# Proiect_TSC_SCHEMATIC.net
KiCad netlist of a schematic drawn in EAGLE
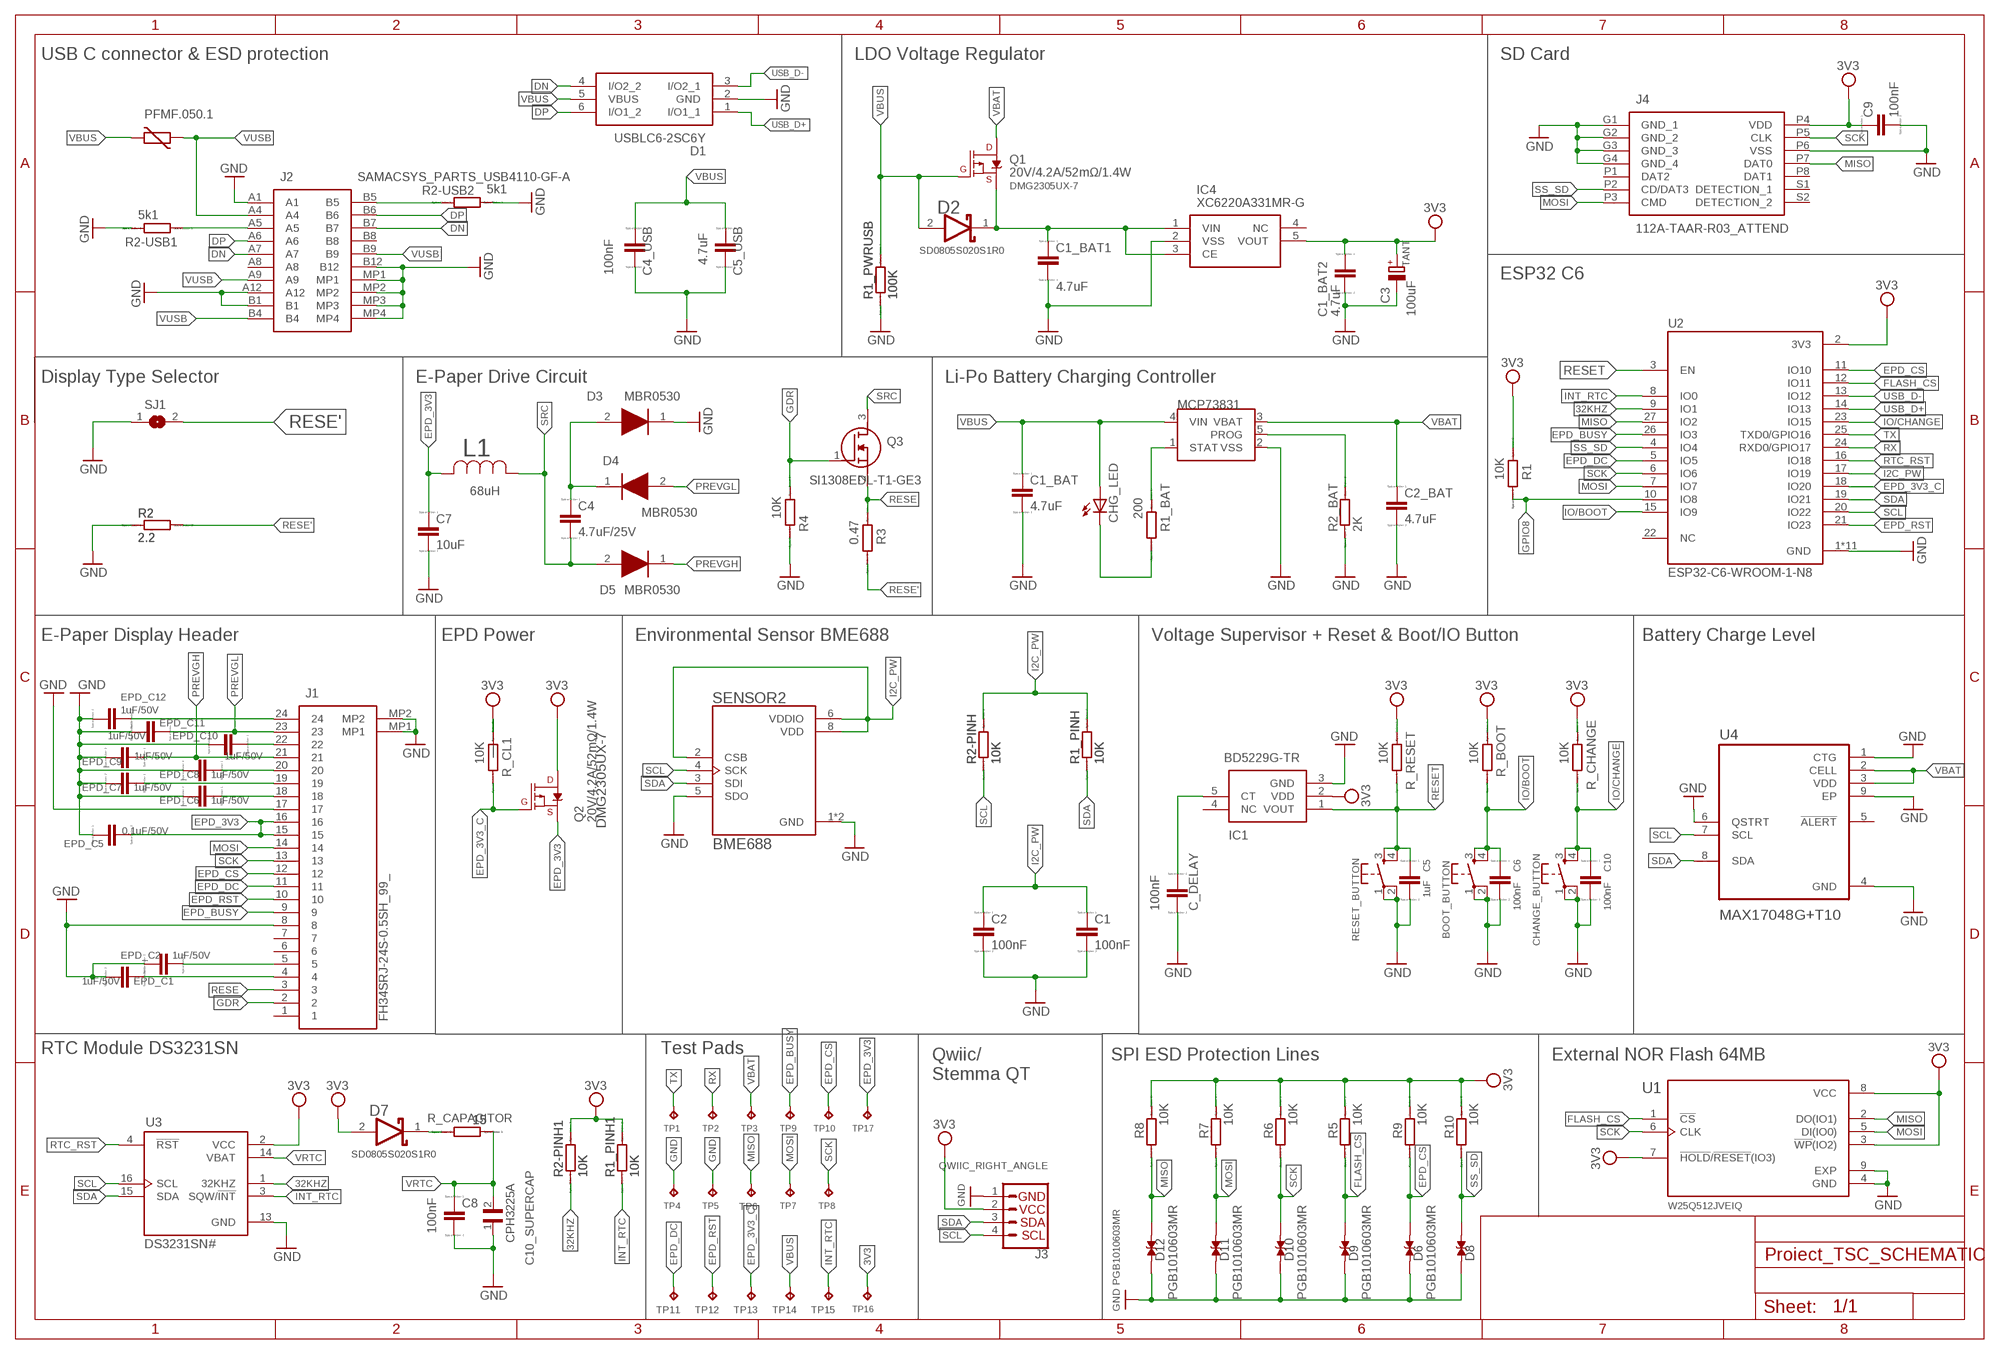
[diagram p0: schematic, sheet 1]

(export (version "E")
  (design (tool "Eeschema 10.0.6"))
  (components
    (comp (ref "BOOT_BUTTON")
      (value "BUTTON_CUSYOMV1")
      (footprint "eagle-import:MYBUTTON")
      (libsource (lib "eagle-import") (part "BUTTON_CUSYOMV1"))
    )
    (comp (ref "C1")
      (value "100nF")
      (footprint "eagle-import:ESP32_WROVER_EAGLE-LTSPICE_C0402")
      (libsource (lib "eagle-import") (part "ESP32_WROVER_EAGLE-LTSPICE_CC0402"))
    )
    (comp (ref "C1_BAT")
      (value "4.7uF")
      (footprint "eagle-import:ESP32_WROVER_EAGLE-LTSPICE_C0402")
      (libsource (lib "eagle-import") (part "ESP32_WROVER_EAGLE-LTSPICE_CC0402"))
    )
    (comp (ref "C1_BAT1")
      (value "4.7uF")
      (footprint "eagle-import:ESP32_WROVER_EAGLE-LTSPICE_C0402")
      (libsource (lib "eagle-import") (part "ESP32_WROVER_EAGLE-LTSPICE_CC0402"))
    )
    (comp (ref "C1_BAT2")
      (value "4.7uF")
      (footprint "eagle-import:ESP32_WROVER_EAGLE-LTSPICE_C0402")
      (libsource (lib "eagle-import") (part "ESP32_WROVER_EAGLE-LTSPICE_CC0402"))
    )
    (comp (ref "C2")
      (value "100nF")
      (footprint "eagle-import:ESP32_WROVER_EAGLE-LTSPICE_C0402")
      (libsource (lib "eagle-import") (part "ESP32_WROVER_EAGLE-LTSPICE_CC0402"))
    )
    (comp (ref "C2_BAT")
      (value "4.7uF")
      (footprint "eagle-import:ESP32_WROVER_EAGLE-LTSPICE_C0402")
      (libsource (lib "eagle-import") (part "ESP32_WROVER_EAGLE-LTSPICE_CC0402"))
    )
    (comp (ref "C3")
      (value "100uF")
      (footprint "eagle-import:RCL_CT3528")
      (libsource (lib "eagle-import") (part "RCL_CPOL-EUCT3528"))
    )
    (comp (ref "C4")
      (value "4.7uF/25V")
      (footprint "eagle-import:ESP32_WROVER_EAGLE-LTSPICE_C0402")
      (libsource (lib "eagle-import") (part "ESP32_WROVER_EAGLE-LTSPICE_CC0402"))
    )
    (comp (ref "C4_USB")
      (value "100nF")
      (footprint "eagle-import:EAGLE-LTSPICE_C0402")
      (libsource (lib "eagle-import") (part "EAGLE-LTSPICE_CC0402"))
    )
    (comp (ref "C5")
      (value "1uF")
      (footprint "eagle-import:ESP32_WROVER_EAGLE-LTSPICE_C0402")
      (libsource (lib "eagle-import") (part "ESP32_WROVER_EAGLE-LTSPICE_CC0402"))
    )
    (comp (ref "C5_USB")
      (value "4.7uF")
      (footprint "eagle-import:EAGLE-LTSPICE_C0402")
      (libsource (lib "eagle-import") (part "EAGLE-LTSPICE_CC0402"))
    )
    (comp (ref "C6")
      (value "100nF")
      (footprint "eagle-import:ESP32_WROVER_EAGLE-LTSPICE_C0402")
      (libsource (lib "eagle-import") (part "ESP32_WROVER_EAGLE-LTSPICE_CC0402"))
    )
    (comp (ref "C7")
      (value "10uF")
      (footprint "eagle-import:ESP32_WROVER_EAGLE-LTSPICE_C0402")
      (libsource (lib "eagle-import") (part "ESP32_WROVER_EAGLE-LTSPICE_CC0402"))
    )
    (comp (ref "C8")
      (value "100nF")
      (footprint "eagle-import:ESP32_WROVER_EAGLE-LTSPICE_C0402")
      (libsource (lib "eagle-import") (part "ESP32_WROVER_EAGLE-LTSPICE_CC0402"))
    )
    (comp (ref "C9")
      (value "100nF")
      (footprint "eagle-import:ESP32_WROVER_EAGLE-LTSPICE_C0402")
      (libsource (lib "eagle-import") (part "ESP32_WROVER_EAGLE-LTSPICE_CC0402"))
    )
    (comp (ref "C10")
      (value "100nF")
      (footprint "eagle-import:ESP32_WROVER_EAGLE-LTSPICE_C0402")
      (libsource (lib "eagle-import") (part "ESP32_WROVER_EAGLE-LTSPICE_CC0402"))
    )
    (comp (ref "C10_SUPERCAP")
      (value "CPH3225A")
      (footprint "eagle-import:CAPCP3225X100N")
      (fields (field (name "MF") "Seiko Instruments"))
      (libsource (lib "eagle-import") (part "CPH3225A"))
    )
    (comp (ref "CHANGE_BUTTON")
      (value "CHANGE_BUTTON")
      (footprint "eagle-import:MYBUTTON")
      (libsource (lib "eagle-import") (part "BUTTON_CUSYOMV1"))
    )
    (comp (ref "CHG_LED")
      (value "ADAFRUIT_LEDCHIP-LED0603")
      (footprint "eagle-import:ADAFRUIT_CHIP-LED0603")
      (libsource (lib "eagle-import") (part "ADAFRUIT_LEDCHIP-LED0603"))
    )
    (comp (ref "C_DELAY")
      (value "100nF")
      (footprint "eagle-import:ESP32_WROVER_EAGLE-LTSPICE_C0402")
      (libsource (lib "eagle-import") (part "ESP32_WROVER_EAGLE-LTSPICE_CC0402"))
    )
    (comp (ref "D1")
      (value "USBLC6-2SC6Y")
      (footprint "eagle-import:SOT95P280X145-6N")
      (fields (field (name "MF") "STMicroelectronics"))
      (libsource (lib "eagle-import") (part "USBLC6-2SC6Y"))
    )
    (comp (ref "D2")
      (value "ESP32_WROVER_AVX---SD0805S020S1R0_AVX_SD0805S020S1R0_0_0AVX_SD0805S020S1R0_0_0")
      (footprint "eagle-import:ESP32_WROVER_AVX---SD0805S020S1R0_AVX_SD0805S020S1R0_0")
      (fields
        (field (name "DIGIKEY_PART_NUMBER") "478-7800-1-ND")
        (field (name "MF") "AVX")
        (field (name "MOUSER_PART_NUMBER") "581-SD0805S020S1R0")
      )
      (libsource (lib "eagle-import") (part "ESP32_WROVER_AVX---SD0805S020S1R0_AVX_SD0805S020S1R0_0_0AVX_SD0805S020S1R0_0_0"))
    )
    (comp (ref "D3")
      (value "MBR0530")
      (footprint "eagle-import:SOD3716X135N")
      (fields (field (name "MF") "ON Semiconductor"))
      (libsource (lib "eagle-import") (part "MBR0530"))
    )
    (comp (ref "D4")
      (value "MBR0530")
      (footprint "eagle-import:SOD3716X135N")
      (fields (field (name "MF") "ON Semiconductor"))
      (libsource (lib "eagle-import") (part "MBR0530"))
    )
    (comp (ref "D5")
      (value "MBR0530")
      (footprint "eagle-import:SOD3716X135N")
      (fields (field (name "MF") "ON Semiconductor"))
      (libsource (lib "eagle-import") (part "MBR0530"))
    )
    (comp (ref "D6")
      (value "PGB1010603MR")
      (footprint "eagle-import:DIOC1608X36N")
      (fields (field (name "MF") "Littelfuse Inc."))
      (libsource (lib "eagle-import") (part "PGB1010603MR"))
    )
    (comp (ref "D7")
      (value "SD0805S020S1R0")
      (footprint "eagle-import:ESP32_WROVER_AVX---SD0805S020S1R0_AVX_SD0805S020S1R0_0")
      (fields
        (field (name "DIGIKEY_PART_NUMBER") "478-7800-1-ND")
        (field (name "MF") "AVX")
        (field (name "MOUSER_PART_NUMBER") "581-SD0805S020S1R0")
      )
      (libsource (lib "eagle-import") (part "ESP32_WROVER_AVX---SD0805S020S1R0_AVX_SD0805S020S1R0_0_0AVX_SD0805S020S1R0_0_0"))
    )
    (comp (ref "D8")
      (value "PGB1010603MR")
      (footprint "eagle-import:DIOC1608X36N")
      (fields (field (name "MF") "Littelfuse Inc."))
      (libsource (lib "eagle-import") (part "PGB1010603MR"))
    )
    (comp (ref "D9")
      (value "PGB1010603MR")
      (footprint "eagle-import:DIOC1608X36N")
      (fields (field (name "MF") "Littelfuse Inc."))
      (libsource (lib "eagle-import") (part "PGB1010603MR"))
    )
    (comp (ref "D10")
      (value "PGB1010603MR")
      (footprint "eagle-import:DIOC1608X36N")
      (fields (field (name "MF") "Littelfuse Inc."))
      (libsource (lib "eagle-import") (part "PGB1010603MR"))
    )
    (comp (ref "D11")
      (value "PGB1010603MR")
      (footprint "eagle-import:DIOC1608X36N")
      (fields (field (name "MF") "Littelfuse Inc."))
      (libsource (lib "eagle-import") (part "PGB1010603MR"))
    )
    (comp (ref "D12")
      (value "PGB1010603MR")
      (footprint "eagle-import:DIOC1608X36N")
      (fields (field (name "MF") "Littelfuse Inc."))
      (libsource (lib "eagle-import") (part "PGB1010603MR"))
    )
    (comp (ref "EPD_C1")
      (value "1uF/50V")
      (footprint "eagle-import:ESP32_WROVER_EAGLE-LTSPICE_C0402")
      (libsource (lib "eagle-import") (part "ESP32_WROVER_EAGLE-LTSPICE_CC0402"))
    )
    (comp (ref "EPD_C2")
      (value "1uF/50V")
      (footprint "eagle-import:ESP32_WROVER_EAGLE-LTSPICE_C0402")
      (libsource (lib "eagle-import") (part "ESP32_WROVER_EAGLE-LTSPICE_CC0402"))
    )
    (comp (ref "EPD_C5")
      (value "0.1uF/50V")
      (footprint "eagle-import:ESP32_WROVER_EAGLE-LTSPICE_C0402")
      (libsource (lib "eagle-import") (part "ESP32_WROVER_EAGLE-LTSPICE_CC0402"))
    )
    (comp (ref "EPD_C6")
      (value "1uF/50V")
      (footprint "eagle-import:ESP32_WROVER_EAGLE-LTSPICE_C0402")
      (libsource (lib "eagle-import") (part "ESP32_WROVER_EAGLE-LTSPICE_CC0402"))
    )
    (comp (ref "EPD_C7")
      (value "1uF/50V")
      (footprint "eagle-import:ESP32_WROVER_EAGLE-LTSPICE_C0402")
      (libsource (lib "eagle-import") (part "ESP32_WROVER_EAGLE-LTSPICE_CC0402"))
    )
    (comp (ref "EPD_C8")
      (value "1uF/50V")
      (footprint "eagle-import:ESP32_WROVER_EAGLE-LTSPICE_C0402")
      (libsource (lib "eagle-import") (part "ESP32_WROVER_EAGLE-LTSPICE_CC0402"))
    )
    (comp (ref "EPD_C9")
      (value "1uF/50V")
      (footprint "eagle-import:ESP32_WROVER_EAGLE-LTSPICE_C0402")
      (libsource (lib "eagle-import") (part "ESP32_WROVER_EAGLE-LTSPICE_CC0402"))
    )
    (comp (ref "EPD_C10")
      (value "1uF/50V")
      (footprint "eagle-import:ESP32_WROVER_EAGLE-LTSPICE_C0402")
      (libsource (lib "eagle-import") (part "ESP32_WROVER_EAGLE-LTSPICE_CC0402"))
    )
    (comp (ref "EPD_C11")
      (value "1uF/50V")
      (footprint "eagle-import:ESP32_WROVER_EAGLE-LTSPICE_C0402")
      (libsource (lib "eagle-import") (part "ESP32_WROVER_EAGLE-LTSPICE_CC0402"))
    )
    (comp (ref "EPD_C12")
      (value "1uF/50V")
      (footprint "eagle-import:ESP32_WROVER_EAGLE-LTSPICE_C0402")
      (libsource (lib "eagle-import") (part "ESP32_WROVER_EAGLE-LTSPICE_CC0402"))
    )
    (comp (ref "IC1")
      (value "BD5229G-TR")
      (footprint "eagle-import:SOT95P280X125-5N")
      (fields (field (name "MOUSER_PART_NUMBER") "755-BD5229G-TR"))
      (libsource (lib "eagle-import") (part "BD5229G-TR"))
    )
    (comp (ref "IC4")
      (value "XC6220A331MR-G")
      (footprint "eagle-import:SOT95P280X120-5N")
      (fields (field (name "MOUSER_PART_NUMBER") "865-XC6220A331MR-G"))
      (libsource (lib "eagle-import") (part "XC6220A331MR-G"))
    )
    (comp (ref "J1")
      (value "FH34SRJ-24S-0.5SH_99_")
      (footprint "eagle-import:FH34SRJ24S05SH99")
      (fields
        (field (name "MANUFACTURER_PART_NUMBER") "FH34SRJ-24S-0.5SH(99)")
        (field (name "MOUSER_PART_NUMBER") "798-FH34SRJ24S05SH99")
      )
      (libsource (lib "eagle-import") (part "FH34SRJ-24S-0.5SH_99_"))
    )
    (comp (ref "J2")
      (value "SAMACSYS_PARTS_USB4110-GF-A")
      (footprint "eagle-import:SAMACSYS_PARTS_USB4110GFA")
      (fields
        (field (name "MANUFACTURER_PART_NUMBER") "USB4110-GF-A")
        (field (name "MOUSER_PART_NUMBER") "640-USB4110-GF-A")
      )
      (libsource (lib "eagle-import") (part "SAMACSYS_PARTS_USB4110-GF-A"))
    )
    (comp (ref "J3")
      (value "QWIIC_RIGHT_ANGLE")
      (footprint "eagle-import:JST04_1MM_RA")
      (libsource (lib "eagle-import") (part "QWIIC_CONNECTORJS-1MM"))
    )
    (comp (ref "J4")
      (value "112A-TAAR-R03_ATTEND")
      (footprint "eagle-import:112ATAARR03ATTEND")
      (fields (field (name "MANUFACTURER_PART_NUMBER") "112A-TAAR-R03 ATTEND"))
      (libsource (lib "eagle-import") (part "112A-TAAR-R03_ATTEND"))
    )
    (comp (ref "L1")
      (value "68uH")
      (footprint "eagle-import:IND_4828-WE-TPC_WRE")
      (fields
        (field (name "MANUFACTURER_PART_NUMBER") "744043680")
        (field (name "COPYRIGHT") "Copyright (C) 2024 Ultra Librarian. All rights reserved.")
      )
      (libsource (lib "eagle-import") (part "744043680IND_4828-WE-TPC_WRE"))
    )
    (comp (ref "MCP73831")
      (value "MCP73831")
      (footprint "eagle-import:ESP32_WROVER_SPARKFUN-IC-POWER_SOT23-5")
      (libsource (lib "eagle-import") (part "ESP32_WROVER_SPARKFUN-IC-POWER_MCP73831"))
    )
    (comp (ref "PFMF.050.1")
      (value "ESP32C6_VARISTORCN1812")
      (footprint "eagle-import:ESP32C6_VARISTOR_CT_CN1812")
      (libsource (lib "eagle-import") (part "ESP32C6_VARISTORCN1812"))
    )
    (comp (ref "Q1")
      (value "20V/4.2A/52mΩ/1.4W")
      (footprint "eagle-import:ESP32_WROVER_SPARKFUN-DISCRETESEMI_SOT23-3")
      (libsource (lib "eagle-import") (part "ESP32_WROVER_SPARKFUN-DISCRETESEMI_MOSFET_PCH-DMG2305UX-7"))
    )
    (comp (ref "Q2")
      (value "20V/4.2A/52mΩ/1.4W")
      (footprint "eagle-import:ESP32_WROVER_SPARKFUN-DISCRETESEMI_SOT23-3")
      (libsource (lib "eagle-import") (part "ESP32_WROVER_SPARKFUN-DISCRETESEMI_MOSFET_PCH-DMG2305UX-7"))
    )
    (comp (ref "Q3")
      (value "SI1308EDL-T1-GE3")
      (footprint "eagle-import:SOT65P210X110-3N")
      (fields (field (name "MF") "Vishay Siliconix"))
      (libsource (lib "eagle-import") (part "SI1308EDL-T1-GE3"))
    )
    (comp (ref "R1")
      (value "10K")
      (footprint "eagle-import:ESP32_WROVER_EAGLE-LTSPICE_R0402")
      (libsource (lib "eagle-import") (part "ESP32_WROVER_EAGLE-LTSPICE_RR0402"))
    )
    (comp (ref "R1_BAT")
      (value "200")
      (footprint "eagle-import:ESP32_WROVER_EAGLE-LTSPICE_R0402")
      (libsource (lib "eagle-import") (part "ESP32_WROVER_EAGLE-LTSPICE_RR0402"))
    )
    (comp (ref "R1_PINH")
      (value "10K")
      (footprint "eagle-import:ESP32_WROVER_EAGLE-LTSPICE_R0402")
      (libsource (lib "eagle-import") (part "ESP32_WROVER_EAGLE-LTSPICE_RR0402"))
    )
    (comp (ref "R1_PINH1")
      (value "10K")
      (footprint "eagle-import:ESP32_WROVER_EAGLE-LTSPICE_R0402")
      (libsource (lib "eagle-import") (part "ESP32_WROVER_EAGLE-LTSPICE_RR0402"))
    )
    (comp (ref "R1_PWRUSB")
      (value "100K")
      (footprint "eagle-import:ESP32_WROVER_EAGLE-LTSPICE_R0402")
      (libsource (lib "eagle-import") (part "ESP32_WROVER_EAGLE-LTSPICE_RR0402"))
    )
    (comp (ref "R2")
      (value "2.2")
      (footprint "eagle-import:ESP32_WROVER_EAGLE-LTSPICE_R0402")
      (libsource (lib "eagle-import") (part "ESP32_WROVER_EAGLE-LTSPICE_RR0402"))
    )
    (comp (ref "R2-PINH")
      (value "10K")
      (footprint "eagle-import:ESP32_WROVER_EAGLE-LTSPICE_R0402")
      (libsource (lib "eagle-import") (part "ESP32_WROVER_EAGLE-LTSPICE_RR0402"))
    )
    (comp (ref "R2-PINH1")
      (value "10K")
      (footprint "eagle-import:ESP32_WROVER_EAGLE-LTSPICE_R0402")
      (libsource (lib "eagle-import") (part "ESP32_WROVER_EAGLE-LTSPICE_RR0402"))
    )
    (comp (ref "R2-USB1")
      (value "5k1")
      (footprint "eagle-import:ESP32_WROVER_EAGLE-LTSPICE_R0402")
      (libsource (lib "eagle-import") (part "ESP32_WROVER_EAGLE-LTSPICE_RR0402"))
    )
    (comp (ref "R2-USB2")
      (value "5k1")
      (footprint "eagle-import:ESP32_WROVER_EAGLE-LTSPICE_R0402")
      (libsource (lib "eagle-import") (part "ESP32_WROVER_EAGLE-LTSPICE_RR0402"))
    )
    (comp (ref "R2_BAT")
      (value "2K")
      (footprint "eagle-import:ESP32_WROVER_EAGLE-LTSPICE_R0402")
      (libsource (lib "eagle-import") (part "ESP32_WROVER_EAGLE-LTSPICE_RR0402"))
    )
    (comp (ref "R3")
      (value "0.47")
      (footprint "eagle-import:ESP32_WROVER_EAGLE-LTSPICE_R0402")
      (libsource (lib "eagle-import") (part "ESP32_WROVER_EAGLE-LTSPICE_RR0402"))
    )
    (comp (ref "R4")
      (value "10K")
      (footprint "eagle-import:ESP32_WROVER_EAGLE-LTSPICE_R0402")
      (libsource (lib "eagle-import") (part "ESP32_WROVER_EAGLE-LTSPICE_RR0402"))
    )
    (comp (ref "R5")
      (value "10K")
      (footprint "eagle-import:ESP32_WROVER_EAGLE-LTSPICE_R0402")
      (libsource (lib "eagle-import") (part "ESP32_WROVER_EAGLE-LTSPICE_RR0402"))
    )
    (comp (ref "R6")
      (value "10K")
      (footprint "eagle-import:ESP32_WROVER_EAGLE-LTSPICE_R0402")
      (libsource (lib "eagle-import") (part "ESP32_WROVER_EAGLE-LTSPICE_RR0402"))
    )
    (comp (ref "R7")
      (value "10K")
      (footprint "eagle-import:ESP32_WROVER_EAGLE-LTSPICE_R0402")
      (libsource (lib "eagle-import") (part "ESP32_WROVER_EAGLE-LTSPICE_RR0402"))
    )
    (comp (ref "R8")
      (value "10K")
      (footprint "eagle-import:ESP32_WROVER_EAGLE-LTSPICE_R0402")
      (libsource (lib "eagle-import") (part "ESP32_WROVER_EAGLE-LTSPICE_RR0402"))
    )
    (comp (ref "R9")
      (value "10K")
      (footprint "eagle-import:ESP32_WROVER_EAGLE-LTSPICE_R0402")
      (libsource (lib "eagle-import") (part "ESP32_WROVER_EAGLE-LTSPICE_RR0402"))
    )
    (comp (ref "R10")
      (value "10K")
      (footprint "eagle-import:ESP32_WROVER_EAGLE-LTSPICE_R0402")
      (libsource (lib "eagle-import") (part "ESP32_WROVER_EAGLE-LTSPICE_RR0402"))
    )
    (comp (ref "RESET_BUTTON")
      (value "BUTTON_CUSYOMV1")
      (footprint "eagle-import:MYBUTTON")
      (libsource (lib "eagle-import") (part "BUTTON_CUSYOMV1"))
    )
    (comp (ref "R_BOOT")
      (value "10K")
      (footprint "eagle-import:ESP32_WROVER_EAGLE-LTSPICE_R0402")
      (libsource (lib "eagle-import") (part "ESP32_WROVER_EAGLE-LTSPICE_RR0402"))
    )
    (comp (ref "R_CAPACITOR")
      (value "15")
      (footprint "eagle-import:ESP32_WROVER_EAGLE-LTSPICE_R0402")
      (libsource (lib "eagle-import") (part "ESP32_WROVER_EAGLE-LTSPICE_RR0402"))
    )
    (comp (ref "R_CHANGE")
      (value "10K")
      (footprint "eagle-import:ESP32_WROVER_EAGLE-LTSPICE_R0402")
      (libsource (lib "eagle-import") (part "ESP32_WROVER_EAGLE-LTSPICE_RR0402"))
    )
    (comp (ref "R_CL1")
      (value "10K")
      (footprint "eagle-import:ESP32_WROVER_EAGLE-LTSPICE_R0402")
      (libsource (lib "eagle-import") (part "ESP32_WROVER_EAGLE-LTSPICE_RR0402"))
    )
    (comp (ref "R_RESET")
      (value "10K")
      (footprint "eagle-import:ESP32_WROVER_EAGLE-LTSPICE_R0402")
      (libsource (lib "eagle-import") (part "ESP32_WROVER_EAGLE-LTSPICE_RR0402"))
    )
    (comp (ref "SENSOR2")
      (value "BME688")
      (footprint "eagle-import:ESP32_WROVER_BME680_PSON80P300X300X100-8N")
      (fields (field (name "MF") "Bosch Sensortec") (field (name "MP") "BME680"))
      (libsource (lib "eagle-import") (part "ESP32_WROVER_BME680_BME680"))
    )
    (comp (ref "SJ1") (value "0") (footprint "eagle-import:SJ") (libsource (lib "eagle-import") (part "SJ")))
    (comp (ref "TP1")
      (value "TPTP20R")
      (footprint "eagle-import:TP20R")
      (libsource (lib "eagle-import") (part "TPTP20R"))
    )
    (comp (ref "TP2")
      (value "TPTP20R")
      (footprint "eagle-import:TP20R")
      (libsource (lib "eagle-import") (part "TPTP20R"))
    )
    (comp (ref "TP3")
      (value "TPTP20R")
      (footprint "eagle-import:TP20R")
      (libsource (lib "eagle-import") (part "TPTP20R"))
    )
    (comp (ref "TP4")
      (value "TPTP20R")
      (footprint "eagle-import:TP20R")
      (libsource (lib "eagle-import") (part "TPTP20R"))
    )
    (comp (ref "TP5")
      (value "TPTP20R")
      (footprint "eagle-import:TP20R")
      (libsource (lib "eagle-import") (part "TPTP20R"))
    )
    (comp (ref "TP6")
      (value "TPTP20R")
      (footprint "eagle-import:TP20R")
      (libsource (lib "eagle-import") (part "TPTP20R"))
    )
    (comp (ref "TP7")
      (value "TPTP20R")
      (footprint "eagle-import:TP20R")
      (libsource (lib "eagle-import") (part "TPTP20R"))
    )
    (comp (ref "TP8")
      (value "TPTP20R")
      (footprint "eagle-import:TP20R")
      (libsource (lib "eagle-import") (part "TPTP20R"))
    )
    (comp (ref "TP9")
      (value "TPTP20R")
      (footprint "eagle-import:TP20R")
      (libsource (lib "eagle-import") (part "TPTP20R"))
    )
    (comp (ref "TP10")
      (value "TPTP20R")
      (footprint "eagle-import:TP20R")
      (libsource (lib "eagle-import") (part "TPTP20R"))
    )
    (comp (ref "TP11")
      (value "TPTP20R")
      (footprint "eagle-import:TP20R")
      (libsource (lib "eagle-import") (part "TPTP20R"))
    )
    (comp (ref "TP12")
      (value "TPTP20R")
      (footprint "eagle-import:TP20R")
      (libsource (lib "eagle-import") (part "TPTP20R"))
    )
    (comp (ref "TP13")
      (value "TPTP20R")
      (footprint "eagle-import:TP20R")
      (libsource (lib "eagle-import") (part "TPTP20R"))
    )
    (comp (ref "TP14")
      (value "TPTP20R")
      (footprint "eagle-import:TP20R")
      (libsource (lib "eagle-import") (part "TPTP20R"))
    )
    (comp (ref "TP15")
      (value "TPTP20R")
      (footprint "eagle-import:TP20R")
      (libsource (lib "eagle-import") (part "TPTP20R"))
    )
    (comp (ref "TP16")
      (value "TPTP20R")
      (footprint "eagle-import:TP20R")
      (libsource (lib "eagle-import") (part "TPTP20R"))
    )
    (comp (ref "TP17")
      (value "TPTP20R")
      (footprint "eagle-import:TP20R")
      (libsource (lib "eagle-import") (part "TPTP20R"))
    )
    (comp (ref "U1")
      (value "W25Q512JVEIQ")
      (footprint "eagle-import:SON127P600X800X80-9N")
      (fields (field (name "MF") "Winbond Electronics"))
      (libsource (lib "eagle-import") (part "W25Q512JVEIQ"))
    )
    (comp (ref "U2")
      (value "ESP32-C6-WROOM-1-N8")
      (footprint "eagle-import:XCVR_ESP32-C6-WROOM-1-N8")
      (fields (field (name "MF") "Espressif Systems"))
      (libsource (lib "eagle-import") (part "ESP32-C6-WROOM-1-N8"))
    )
    (comp (ref "U3")
      (value "DS3231SN#")
      (footprint "eagle-import:SOIC127P1032X265-16N")
      (fields (field (name "MF") "Analog Devices"))
      (libsource (lib "eagle-import") (part "DS3231SN#"))
    )
    (comp (ref "U4")
      (value "MAX17048G+T10")
      (footprint "eagle-import:SON50P200X200X80-9N")
      (fields (field (name "MF") "Analog Devices"))
      (libsource (lib "eagle-import") (part "MAX17048G+T10"))
    )
  )
  (nets
    (net (code "1") (name "3V3") (class "Default")
      (node (ref "C1_BAT2") (pin "1") (pinfunction "1_1") (pintype "passive"))
      (node (ref "C3") (pin "+") (pinfunction "+_+") (pintype "passive"))
      (node (ref "C9") (pin "1") (pinfunction "1_1") (pintype "passive"))
      (node (ref "D7") (pin "2") (pinfunction "ANODE_2") (pintype "bidirectional"))
      (node (ref "IC1") (pin "2") (pinfunction "VDD_2") (pintype "bidirectional"))
      (node (ref "IC4") (pin "5") (pinfunction "VOUT_5") (pintype "bidirectional"))
      (node (ref "J3") (pin "2") (pinfunction "2_2") (pintype "power_in"))
      (node (ref "J4") (pin "P4") (pinfunction "VDD_P4") (pintype "bidirectional"))
      (node (ref "Q2") (pin "3") (pinfunction "D_3") (pintype "bidirectional"))
      (node (ref "R1") (pin "2") (pinfunction "2_2") (pintype "passive"))
      (node (ref "R10") (pin "2") (pinfunction "2_2") (pintype "passive"))
      (node (ref "R1_PINH1") (pin "2") (pinfunction "2_2") (pintype "passive"))
      (node (ref "R2-PINH1") (pin "2") (pinfunction "2_2") (pintype "passive"))
      (node (ref "R5") (pin "2") (pinfunction "2_2") (pintype "passive"))
      (node (ref "R6") (pin "2") (pinfunction "2_2") (pintype "passive"))
      (node (ref "R7") (pin "2") (pinfunction "2_2") (pintype "passive"))
      (node (ref "R8") (pin "2") (pinfunction "2_2") (pintype "passive"))
      (node (ref "R9") (pin "2") (pinfunction "2_2") (pintype "passive"))
      (node (ref "R_BOOT") (pin "2") (pinfunction "2_2") (pintype "passive"))
      (node (ref "R_CHANGE") (pin "2") (pinfunction "2_2") (pintype "passive"))
      (node (ref "R_CL1") (pin "2") (pinfunction "2_2") (pintype "passive"))
      (node (ref "R_RESET") (pin "2") (pinfunction "2_2") (pintype "passive"))
      (node (ref "TP16") (pin "TP") (pinfunction "TP_TP") (pintype "input"))
      (node (ref "U1") (pin "3") (pinfunction "~{WP}(IO2)_3") (pintype "bidirectional"))
      (node (ref "U1") (pin "7") (pinfunction "~{HOLD}/~{RESET}(IO3)_7") (pintype "bidirectional"))
      (node (ref "U1") (pin "8") (pinfunction "VCC_8") (pintype "power_in"))
      (node (ref "U2") (pin "2") (pinfunction "3V3_2") (pintype "power_in"))
      (node (ref "U3") (pin "2") (pinfunction "VCC_2") (pintype "power_in"))
    )
    (net (code "2") (name "32KHZ") (class "Default")
      (node (ref "R2-PINH1") (pin "1") (pinfunction "1_1") (pintype "passive"))
      (node (ref "U2") (pin "9") (pinfunction "IO1_9") (pintype "bidirectional"))
      (node (ref "U3") (pin "1") (pinfunction "32KHZ_1") (pintype "output"))
    )
    (net (code "3") (name "DN") (class "Default")
      (node (ref "D1") (pin "4") (pinfunction "I/O2_2_4") (pintype "bidirectional"))
      (node (ref "J2") (pin "A7") (pinfunction "A7_A7") (pintype "bidirectional"))
      (node (ref "J2") (pin "B7") (pinfunction "B7_B7") (pintype "bidirectional"))
    )
    (net (code "4") (name "DP") (class "Default")
      (node (ref "D1") (pin "6") (pinfunction "I/O1_2_6") (pintype "bidirectional"))
      (node (ref "J2") (pin "A6") (pinfunction "A6_A6") (pintype "bidirectional"))
      (node (ref "J2") (pin "B6") (pinfunction "B6_B6") (pintype "bidirectional"))
    )
    (net (code "5") (name "EPD_3V3") (class "Default")
      (node (ref "C7") (pin "1") (pinfunction "1_1") (pintype "passive"))
      (node (ref "EPD_C5") (pin "2") (pinfunction "2_2") (pintype "passive"))
      (node (ref "J1") (pin "15") (pinfunction "15_15") (pintype "bidirectional"))
      (node (ref "J1") (pin "16") (pinfunction "16_16") (pintype "bidirectional"))
      (node (ref "L1") (pin "2") (pinfunction "2_2") (pintype "passive"))
      (node (ref "Q2") (pin "2") (pinfunction "S_2") (pintype "bidirectional"))
      (node (ref "TP17") (pin "TP") (pinfunction "TP_TP") (pintype "input"))
    )
    (net (code "6") (name "EPD_3V3_C") (class "Default")
      (node (ref "Q2") (pin "1") (pinfunction "G_1") (pintype "bidirectional"))
      (node (ref "R_CL1") (pin "1") (pinfunction "1_1") (pintype "passive"))
      (node (ref "TP13") (pin "TP") (pinfunction "TP_TP") (pintype "input"))
      (node (ref "U2") (pin "18") (pinfunction "IO20_18") (pintype "bidirectional"))
    )
    (net (code "7") (name "EPD_BUSY") (class "Default")
      (node (ref "J1") (pin "9") (pinfunction "9_9") (pintype "bidirectional"))
      (node (ref "TP9") (pin "TP") (pinfunction "TP_TP") (pintype "input"))
      (node (ref "U2") (pin "26") (pinfunction "IO3_26") (pintype "bidirectional"))
    )
    (net (code "8") (name "EPD_CS") (class "Default")
      (node (ref "D6") (pin "2") (pinfunction "2_2") (pintype "passive"))
      (node (ref "J1") (pin "12") (pinfunction "12_12") (pintype "bidirectional"))
      (node (ref "R9") (pin "1") (pinfunction "1_1") (pintype "passive"))
      (node (ref "TP10") (pin "TP") (pinfunction "TP_TP") (pintype "input"))
      (node (ref "U2") (pin "11") (pinfunction "IO10_11") (pintype "bidirectional"))
    )
    (net (code "9") (name "EPD_DC") (class "Default")
      (node (ref "J1") (pin "11") (pinfunction "11_11") (pintype "bidirectional"))
      (node (ref "TP11") (pin "TP") (pinfunction "TP_TP") (pintype "input"))
      (node (ref "U2") (pin "5") (pinfunction "IO5_5") (pintype "bidirectional"))
    )
    (net (code "10") (name "EPD_RST") (class "Default")
      (node (ref "J1") (pin "10") (pinfunction "10_10") (pintype "bidirectional"))
      (node (ref "TP12") (pin "TP") (pinfunction "TP_TP") (pintype "input"))
      (node (ref "U2") (pin "21") (pinfunction "IO23_21") (pintype "bidirectional"))
    )
    (net (code "11") (name "FLASH_CS") (class "Default")
      (node (ref "D9") (pin "2") (pinfunction "2_2") (pintype "passive"))
      (node (ref "R5") (pin "1") (pinfunction "1_1") (pintype "passive"))
      (node (ref "U1") (pin "1") (pinfunction "~{CS}_1") (pintype "input"))
      (node (ref "U2") (pin "12") (pinfunction "IO11_12") (pintype "bidirectional"))
    )
    (net (code "12") (name "GDR") (class "Default")
      (node (ref "J1") (pin "2") (pinfunction "2_2") (pintype "bidirectional"))
      (node (ref "Q3") (pin "1") (pinfunction "G_1") (pintype "bidirectional"))
      (node (ref "R4") (pin "2") (pinfunction "2_2") (pintype "passive"))
    )
    (net (code "13") (name "GND") (class "Default")
      (node (ref "BOOT_BUTTON") (pin "1") (pinfunction "1_1") (pintype "passive"))
      (node (ref "BOOT_BUTTON") (pin "2") (pinfunction "2_2") (pintype "passive"))
      (node (ref "C1") (pin "2") (pinfunction "2_2") (pintype "passive"))
      (node (ref "C10") (pin "2") (pinfunction "2_2") (pintype "passive"))
      (node (ref "C10_SUPERCAP") (pin "1") (pinfunction "1_1") (pintype "passive"))
      (node (ref "C1_BAT") (pin "2") (pinfunction "2_2") (pintype "passive"))
      (node (ref "C1_BAT1") (pin "2") (pinfunction "2_2") (pintype "passive"))
      (node (ref "C1_BAT2") (pin "2") (pinfunction "2_2") (pintype "passive"))
      (node (ref "C2") (pin "2") (pinfunction "2_2") (pintype "passive"))
      (node (ref "C2_BAT") (pin "2") (pinfunction "2_2") (pintype "passive"))
      (node (ref "C3") (pin "-") (pinfunction "-_-") (pintype "passive"))
      (node (ref "C4_USB") (pin "2") (pinfunction "2_2") (pintype "passive"))
      (node (ref "C5") (pin "2") (pinfunction "2_2") (pintype "passive"))
      (node (ref "C5_USB") (pin "2") (pinfunction "2_2") (pintype "passive"))
      (node (ref "C6") (pin "2") (pinfunction "2_2") (pintype "passive"))
      (node (ref "C7") (pin "2") (pinfunction "2_2") (pintype "passive"))
      (node (ref "C8") (pin "2") (pinfunction "2_2") (pintype "passive"))
      (node (ref "C9") (pin "2") (pinfunction "2_2") (pintype "passive"))
      (node (ref "CHANGE_BUTTON") (pin "1") (pinfunction "1_1") (pintype "passive"))
      (node (ref "CHANGE_BUTTON") (pin "2") (pinfunction "2_2") (pintype "passive"))
      (node (ref "C_DELAY") (pin "2") (pinfunction "2_2") (pintype "passive"))
      (node (ref "D1") (pin "2") (pinfunction "GND_2") (pintype "bidirectional"))
      (node (ref "D10") (pin "1") (pinfunction "1_1") (pintype "passive"))
      (node (ref "D11") (pin "1") (pinfunction "1_1") (pintype "passive"))
      (node (ref "D12") (pin "1") (pinfunction "1_1") (pintype "passive"))
      (node (ref "D3") (pin "1") (pinfunction "K_1") (pintype "bidirectional"))
      (node (ref "D6") (pin "1") (pinfunction "1_1") (pintype "passive"))
      (node (ref "D8") (pin "1") (pinfunction "1_1") (pintype "passive"))
      (node (ref "D9") (pin "1") (pinfunction "1_1") (pintype "passive"))
      (node (ref "EPD_C1") (pin "2") (pinfunction "2_2") (pintype "passive"))
      (node (ref "EPD_C10") (pin "2") (pinfunction "2_2") (pintype "passive"))
      (node (ref "EPD_C11") (pin "2") (pinfunction "2_2") (pintype "passive"))
      (node (ref "EPD_C12") (pin "2") (pinfunction "2_2") (pintype "passive"))
      (node (ref "EPD_C2") (pin "2") (pinfunction "2_2") (pintype "passive"))
      (node (ref "EPD_C5") (pin "1") (pinfunction "1_1") (pintype "passive"))
      (node (ref "EPD_C6") (pin "2") (pinfunction "2_2") (pintype "passive"))
      (node (ref "EPD_C7") (pin "2") (pinfunction "2_2") (pintype "passive"))
      (node (ref "EPD_C8") (pin "2") (pinfunction "2_2") (pintype "passive"))
      (node (ref "EPD_C9") (pin "2") (pinfunction "2_2") (pintype "passive"))
      (node (ref "IC1") (pin "3") (pinfunction "GND_3") (pintype "bidirectional"))
      (node (ref "IC4") (pin "2") (pinfunction "VSS_2") (pintype "bidirectional"))
      (node (ref "J1") (pin "17") (pinfunction "17_17") (pintype "bidirectional"))
      (node (ref "J1") (pin "8") (pinfunction "8_8") (pintype "bidirectional"))
      (node (ref "J1") (pin "MP1") (pinfunction "MP1_MP1") (pintype "bidirectional"))
      (node (ref "J1") (pin "MP2") (pinfunction "MP2_MP2") (pintype "bidirectional"))
      (node (ref "J2") (pin "A1") (pinfunction "A1_A1") (pintype "bidirectional"))
      (node (ref "J2") (pin "A12") (pinfunction "A12_A12") (pintype "bidirectional"))
      (node (ref "J2") (pin "B1") (pinfunction "B1_B1") (pintype "bidirectional"))
      (node (ref "J2") (pin "B12") (pinfunction "B12_B12") (pintype "bidirectional"))
      (node (ref "J2") (pin "MP1") (pinfunction "MP1_MP1") (pintype "bidirectional"))
      (node (ref "J2") (pin "MP2") (pinfunction "MP2_MP2") (pintype "bidirectional"))
      (node (ref "J2") (pin "MP3") (pinfunction "MP3_MP3") (pintype "bidirectional"))
      (node (ref "J2") (pin "MP4") (pinfunction "MP4_MP4") (pintype "bidirectional"))
      (node (ref "J3") (pin "1") (pinfunction "1_1") (pintype "power_in"))
      (node (ref "J4") (pin "G1") (pinfunction "GND_1_G1") (pintype "bidirectional"))
      (node (ref "J4") (pin "G2") (pinfunction "GND_2_G2") (pintype "bidirectional"))
      (node (ref "J4") (pin "G3") (pinfunction "GND_3_G3") (pintype "bidirectional"))
      (node (ref "J4") (pin "G4") (pinfunction "GND_4_G4") (pintype "bidirectional"))
      (node (ref "J4") (pin "P6") (pinfunction "VSS_P6") (pintype "bidirectional"))
      (node (ref "MCP73831") (pin "2") (pinfunction "VSS_2") (pintype "power_in"))
      (node (ref "R1_PWRUSB") (pin "1") (pinfunction "1_1") (pintype "passive"))
      (node (ref "R2") (pin "1") (pinfunction "1_1") (pintype "passive"))
      (node (ref "R2-USB1") (pin "1") (pinfunction "1_1") (pintype "passive"))
      (node (ref "R2-USB2") (pin "2") (pinfunction "2_2") (pintype "passive"))
      (node (ref "R2_BAT") (pin "1") (pinfunction "1_1") (pintype "passive"))
      (node (ref "R4") (pin "1") (pinfunction "1_1") (pintype "passive"))
      (node (ref "RESET_BUTTON") (pin "1") (pinfunction "1_1") (pintype "passive"))
      (node (ref "RESET_BUTTON") (pin "2") (pinfunction "2_2") (pintype "passive"))
      (node (ref "SENSOR2") (pin "1") (pinfunction "GND_1") (pintype "power_in"))
      (node (ref "SENSOR2") (pin "5") (pinfunction "SDO_5") (pintype "bidirectional"))
      (node (ref "SENSOR2") (pin "7") (pinfunction "GND_7") (pintype "power_in"))
      (node (ref "SJ1") (pin "1") (pinfunction "1_1") (pintype "passive"))
      (node (ref "TP4") (pin "TP") (pinfunction "TP_TP") (pintype "input"))
      (node (ref "TP5") (pin "TP") (pinfunction "TP_TP") (pintype "input"))
      (node (ref "U1") (pin "4") (pinfunction "GND_4") (pintype "power_in"))
      (node (ref "U1") (pin "9") (pinfunction "EXP_9") (pintype "passive"))
      (node (ref "U2") (pin "1") (pinfunction "GND_1") (pintype "power_in"))
      (node (ref "U2") (pin "28") (pinfunction "GND_28") (pintype "power_in"))
      (node (ref "U2") (pin "29_1") (pinfunction "GND_29_1") (pintype "power_in"))
      (node (ref "U2") (pin "29_2") (pinfunction "GND_29_2") (pintype "power_in"))
      (node (ref "U2") (pin "29_3") (pinfunction "GND_29_3") (pintype "power_in"))
      (node (ref "U2") (pin "29_4") (pinfunction "GND_29_4") (pintype "power_in"))
      (node (ref "U2") (pin "29_5") (pinfunction "GND_29_5") (pintype "power_in"))
      (node (ref "U2") (pin "29_6") (pinfunction "GND_29_6") (pintype "power_in"))
      (node (ref "U2") (pin "29_7") (pinfunction "GND_29_7") (pintype "power_in"))
      (node (ref "U2") (pin "29_8") (pinfunction "GND_29_8") (pintype "power_in"))
      (node (ref "U2") (pin "29_9") (pinfunction "GND_29_9") (pintype "power_in"))
      (node (ref "U3") (pin "13") (pinfunction "GND_13") (pintype "power_in"))
      (node (ref "U4") (pin "1") (pinfunction "CTG_1") (pintype "power_in"))
      (node (ref "U4") (pin "4") (pinfunction "GND_4") (pintype "power_in"))
      (node (ref "U4") (pin "6") (pinfunction "QSTRT_6") (pintype "input"))
      (node (ref "U4") (pin "9") (pinfunction "EP_9") (pintype "power_in"))
    )
    (net (code "14") (name "GPIO8") (class "Default")
      (node (ref "R1") (pin "1") (pinfunction "1_1") (pintype "passive"))
      (node (ref "U2") (pin "10") (pinfunction "IO8_10") (pintype "bidirectional"))
    )
    (net (code "15") (name "I2C_PW") (class "Default")
      (node (ref "C1") (pin "1") (pinfunction "1_1") (pintype "passive"))
      (node (ref "C2") (pin "1") (pinfunction "1_1") (pintype "passive"))
      (node (ref "R1_PINH") (pin "2") (pinfunction "2_2") (pintype "passive"))
      (node (ref "R2-PINH") (pin "2") (pinfunction "2_2") (pintype "passive"))
      (node (ref "SENSOR2") (pin "2") (pinfunction "CSB_2") (pintype "input"))
      (node (ref "SENSOR2") (pin "6") (pinfunction "VDDIO_6") (pintype "power_in"))
      (node (ref "SENSOR2") (pin "8") (pinfunction "VDD_8") (pintype "power_in"))
      (node (ref "U2") (pin "17") (pinfunction "IO19_17") (pintype "bidirectional"))
    )
    (net (code "16") (name "INT_RTC") (class "Default")
      (node (ref "R1_PINH1") (pin "1") (pinfunction "1_1") (pintype "passive"))
      (node (ref "TP15") (pin "TP") (pinfunction "TP_TP") (pintype "input"))
      (node (ref "U2") (pin "8") (pinfunction "IO0_8") (pintype "bidirectional"))
      (node (ref "U3") (pin "3") (pinfunction "SQW/~{INT}_3") (pintype "output"))
    )
    (net (code "17") (name "IO{slash}BOOT") (class "Default")
      (node (ref "BOOT_BUTTON") (pin "3") (pinfunction "3_3") (pintype "passive"))
      (node (ref "BOOT_BUTTON") (pin "4") (pinfunction "4_4") (pintype "passive"))
      (node (ref "C6") (pin "1") (pinfunction "1_1") (pintype "passive"))
      (node (ref "R_BOOT") (pin "1") (pinfunction "1_1") (pintype "passive"))
      (node (ref "U2") (pin "15") (pinfunction "IO9_15") (pintype "bidirectional"))
    )
    (net (code "18") (name "IO{slash}CHANGE") (class "Default")
      (node (ref "C10") (pin "1") (pinfunction "1_1") (pintype "passive"))
      (node (ref "CHANGE_BUTTON") (pin "3") (pinfunction "3_3") (pintype "passive"))
      (node (ref "CHANGE_BUTTON") (pin "4") (pinfunction "4_4") (pintype "passive"))
      (node (ref "R_CHANGE") (pin "1") (pinfunction "1_1") (pintype "passive"))
      (node (ref "U2") (pin "23") (pinfunction "IO15_23") (pintype "bidirectional"))
    )
    (net (code "19") (name "MISO") (class "Default")
      (node (ref "D12") (pin "2") (pinfunction "2_2") (pintype "passive"))
      (node (ref "J4") (pin "P7") (pinfunction "DAT0_P7") (pintype "bidirectional"))
      (node (ref "R8") (pin "1") (pinfunction "1_1") (pintype "passive"))
      (node (ref "TP6") (pin "TP") (pinfunction "TP_TP") (pintype "input"))
      (node (ref "U1") (pin "2") (pinfunction "DO(IO1)_2") (pintype "bidirectional"))
      (node (ref "U2") (pin "27") (pinfunction "IO2_27") (pintype "bidirectional"))
    )
    (net (code "20") (name "MOSI") (class "Default")
      (node (ref "D11") (pin "2") (pinfunction "2_2") (pintype "passive"))
      (node (ref "J1") (pin "14") (pinfunction "14_14") (pintype "bidirectional"))
      (node (ref "J4") (pin "P3") (pinfunction "CMD_P3") (pintype "bidirectional"))
      (node (ref "R7") (pin "1") (pinfunction "1_1") (pintype "passive"))
      (node (ref "TP7") (pin "TP") (pinfunction "TP_TP") (pintype "input"))
      (node (ref "U1") (pin "5") (pinfunction "DI(IO0)_5") (pintype "bidirectional"))
      (node (ref "U2") (pin "7") (pinfunction "IO7_7") (pintype "bidirectional"))
    )
    (net (code "21") (name "Net-(CHG_LED-PadC)") (class "Default")
      (node (ref "CHG_LED") (pin "C") (pinfunction "C_C") (pintype "passive"))
      (node (ref "R1_BAT") (pin "1") (pinfunction "1_1") (pintype "passive"))
    )
    (net (code "22") (name "Net-(D2-CATHODE)") (class "Default")
      (node (ref "C1_BAT1") (pin "1") (pinfunction "1_1") (pintype "passive"))
      (node (ref "D2") (pin "1") (pinfunction "CATHODE_1") (pintype "bidirectional"))
      (node (ref "IC4") (pin "1") (pinfunction "VIN_1") (pintype "bidirectional"))
      (node (ref "IC4") (pin "3") (pinfunction "CE_3") (pintype "bidirectional"))
      (node (ref "Q1") (pin "2") (pinfunction "S_2") (pintype "bidirectional"))
    )
    (net (code "23") (name "Net-(D3-A)") (class "Default")
      (node (ref "C4") (pin "1") (pinfunction "1_1") (pintype "passive"))
      (node (ref "D3") (pin "2") (pinfunction "A_2") (pintype "bidirectional"))
      (node (ref "D4") (pin "1") (pinfunction "K_1") (pintype "bidirectional"))
    )
    (net (code "24") (name "Net-(D7-CATHODE)") (class "Default")
      (node (ref "D7") (pin "1") (pinfunction "CATHODE_1") (pintype "bidirectional"))
      (node (ref "R_CAPACITOR") (pin "2") (pinfunction "2_2") (pintype "passive"))
    )
    (net (code "25") (name "Net-(EPD_C1-Pad1)") (class "Default")
      (node (ref "EPD_C1") (pin "1") (pinfunction "1_1") (pintype "passive"))
      (node (ref "J1") (pin "4") (pinfunction "4_4") (pintype "bidirectional"))
    )
    (net (code "26") (name "Net-(EPD_C2-Pad1)") (class "Default")
      (node (ref "EPD_C2") (pin "1") (pinfunction "1_1") (pintype "passive"))
      (node (ref "J1") (pin "5") (pinfunction "5_5") (pintype "bidirectional"))
    )
    (net (code "27") (name "Net-(EPD_C6-Pad1)") (class "Default")
      (node (ref "EPD_C6") (pin "1") (pinfunction "1_1") (pintype "passive"))
      (node (ref "J1") (pin "18") (pinfunction "18_18") (pintype "bidirectional"))
    )
    (net (code "28") (name "Net-(EPD_C7-Pad1)") (class "Default")
      (node (ref "EPD_C7") (pin "1") (pinfunction "1_1") (pintype "passive"))
      (node (ref "J1") (pin "19") (pinfunction "19_19") (pintype "bidirectional"))
    )
    (net (code "29") (name "Net-(EPD_C8-Pad1)") (class "Default")
      (node (ref "EPD_C8") (pin "1") (pinfunction "1_1") (pintype "passive"))
      (node (ref "J1") (pin "20") (pinfunction "20_20") (pintype "bidirectional"))
    )
    (net (code "30") (name "Net-(EPD_C10-Pad1)") (class "Default")
      (node (ref "EPD_C10") (pin "1") (pinfunction "1_1") (pintype "passive"))
      (node (ref "J1") (pin "22") (pinfunction "22_22") (pintype "bidirectional"))
    )
    (net (code "31") (name "Net-(EPD_C12-Pad1)") (class "Default")
      (node (ref "EPD_C12") (pin "1") (pinfunction "1_1") (pintype "passive"))
      (node (ref "J1") (pin "24") (pinfunction "24_24") (pintype "bidirectional"))
    )
    (net (code "32") (name "Net-(IC1-CT)") (class "Default")
      (node (ref "C_DELAY") (pin "1") (pinfunction "1_1") (pintype "passive"))
      (node (ref "IC1") (pin "5") (pinfunction "CT_5") (pintype "bidirectional"))
    )
    (net (code "33") (name "Net-(J2-PadA5)") (class "Default")
      (node (ref "J2") (pin "A5") (pinfunction "A5_A5") (pintype "bidirectional"))
      (node (ref "R2-USB1") (pin "2") (pinfunction "2_2") (pintype "passive"))
    )
    (net (code "34") (name "Net-(J2-PadB5)") (class "Default")
      (node (ref "J2") (pin "B5") (pinfunction "B5_B5") (pintype "bidirectional"))
      (node (ref "R2-USB2") (pin "1") (pinfunction "1_1") (pintype "passive"))
    )
    (net (code "35") (name "Net-(MCP73831-PROG)") (class "Default")
      (node (ref "MCP73831") (pin "5") (pinfunction "PROG_5") (pintype "input"))
      (node (ref "R2_BAT") (pin "2") (pinfunction "2_2") (pintype "passive"))
    )
    (net (code "36") (name "Net-(MCP73831-STAT)") (class "Default")
      (node (ref "MCP73831") (pin "1") (pinfunction "STAT_1") (pintype "output"))
      (node (ref "R1_BAT") (pin "2") (pinfunction "2_2") (pintype "passive"))
    )
    (net (code "37") (name "PREVGH") (class "Default")
      (node (ref "D5") (pin "1") (pinfunction "K_1") (pintype "bidirectional"))
      (node (ref "EPD_C9") (pin "1") (pinfunction "1_1") (pintype "passive"))
      (node (ref "J1") (pin "21") (pinfunction "21_21") (pintype "bidirectional"))
    )
    (net (code "38") (name "PREVGL") (class "Default")
      (node (ref "D4") (pin "2") (pinfunction "A_2") (pintype "bidirectional"))
      (node (ref "EPD_C11") (pin "1") (pinfunction "1_1") (pintype "passive"))
      (node (ref "J1") (pin "23") (pinfunction "23_23") (pintype "bidirectional"))
    )
    (net (code "39") (name "RESE") (class "Default")
      (node (ref "J1") (pin "3") (pinfunction "3_3") (pintype "bidirectional"))
      (node (ref "Q3") (pin "2") (pinfunction "S_2") (pintype "bidirectional"))
      (node (ref "R3") (pin "2") (pinfunction "2_2") (pintype "passive"))
    )
    (net (code "40") (name "RESE'") (class "Default")
      (node (ref "R2") (pin "2") (pinfunction "2_2") (pintype "passive"))
      (node (ref "R3") (pin "1") (pinfunction "1_1") (pintype "passive"))
      (node (ref "SJ1") (pin "2") (pinfunction "2_2") (pintype "passive"))
    )
    (net (code "41") (name "RESET") (class "Default")
      (node (ref "C5") (pin "1") (pinfunction "1_1") (pintype "passive"))
      (node (ref "IC1") (pin "1") (pinfunction "VOUT_1") (pintype "bidirectional"))
      (node (ref "RESET_BUTTON") (pin "3") (pinfunction "3_3") (pintype "passive"))
      (node (ref "RESET_BUTTON") (pin "4") (pinfunction "4_4") (pintype "passive"))
      (node (ref "R_RESET") (pin "1") (pinfunction "1_1") (pintype "passive"))
      (node (ref "U2") (pin "3") (pinfunction "EN_3") (pintype "input"))
    )
    (net (code "42") (name "RTC_RST") (class "Default")
      (node (ref "U2") (pin "16") (pinfunction "IO18_16") (pintype "bidirectional"))
      (node (ref "U3") (pin "4") (pinfunction "~{RST}_4") (pintype "input"))
    )
    (net (code "43") (name "RX") (class "Default")
      (node (ref "TP2") (pin "TP") (pinfunction "TP_TP") (pintype "input"))
      (node (ref "U2") (pin "24") (pinfunction "RXD0/GPIO17_24") (pintype "bidirectional"))
    )
    (net (code "44") (name "SCK") (class "Default")
      (node (ref "D10") (pin "2") (pinfunction "2_2") (pintype "passive"))
      (node (ref "J1") (pin "13") (pinfunction "13_13") (pintype "bidirectional"))
      (node (ref "J4") (pin "P5") (pinfunction "CLK_P5") (pintype "bidirectional"))
      (node (ref "R6") (pin "1") (pinfunction "1_1") (pintype "passive"))
      (node (ref "TP8") (pin "TP") (pinfunction "TP_TP") (pintype "input"))
      (node (ref "U1") (pin "6") (pinfunction "CLK_6") (pintype "input"))
      (node (ref "U2") (pin "6") (pinfunction "IO6_6") (pintype "bidirectional"))
    )
    (net (code "45") (name "SCL") (class "Default")
      (node (ref "J3") (pin "4") (pinfunction "4_4") (pintype "passive"))
      (node (ref "R2-PINH") (pin "1") (pinfunction "1_1") (pintype "passive"))
      (node (ref "SENSOR2") (pin "4") (pinfunction "SCK_4") (pintype "input"))
      (node (ref "U2") (pin "20") (pinfunction "IO22_20") (pintype "bidirectional"))
      (node (ref "U3") (pin "16") (pinfunction "SCL_16") (pintype "input"))
      (node (ref "U4") (pin "7") (pinfunction "SCL_7") (pintype "input"))
    )
    (net (code "46") (name "SDA") (class "Default")
      (node (ref "J3") (pin "3") (pinfunction "3_3") (pintype "passive"))
      (node (ref "R1_PINH") (pin "1") (pinfunction "1_1") (pintype "passive"))
      (node (ref "SENSOR2") (pin "3") (pinfunction "SDI_3") (pintype "bidirectional"))
      (node (ref "U2") (pin "19") (pinfunction "IO21_19") (pintype "bidirectional"))
      (node (ref "U3") (pin "15") (pinfunction "SDA_15") (pintype "bidirectional"))
      (node (ref "U4") (pin "8") (pinfunction "SDA_8") (pintype "bidirectional"))
    )
    (net (code "47") (name "SRC") (class "Default")
      (node (ref "C4") (pin "2") (pinfunction "2_2") (pintype "passive"))
      (node (ref "D5") (pin "2") (pinfunction "A_2") (pintype "bidirectional"))
      (node (ref "L1") (pin "1") (pinfunction "1_1") (pintype "passive"))
      (node (ref "Q3") (pin "3") (pinfunction "D_3") (pintype "bidirectional"))
    )
    (net (code "48") (name "SS_SD") (class "Default")
      (node (ref "D8") (pin "2") (pinfunction "2_2") (pintype "passive"))
      (node (ref "J4") (pin "P2") (pinfunction "CD/DAT3_P2") (pintype "bidirectional"))
      (node (ref "R10") (pin "1") (pinfunction "1_1") (pintype "passive"))
      (node (ref "U2") (pin "4") (pinfunction "IO4_4") (pintype "bidirectional"))
    )
    (net (code "49") (name "TX") (class "Default")
      (node (ref "TP1") (pin "TP") (pinfunction "TP_TP") (pintype "input"))
      (node (ref "U2") (pin "25") (pinfunction "TXD0/GPIO16_25") (pintype "bidirectional"))
    )
    (net (code "50") (name "USB_D+") (class "Default")
      (node (ref "D1") (pin "1") (pinfunction "I/O1_1_1") (pintype "bidirectional"))
      (node (ref "U2") (pin "14") (pinfunction "IO13_14") (pintype "bidirectional"))
    )
    (net (code "51") (name "USB_D-") (class "Default")
      (node (ref "D1") (pin "3") (pinfunction "I/O2_1_3") (pintype "bidirectional"))
      (node (ref "U2") (pin "13") (pinfunction "IO12_13") (pintype "bidirectional"))
    )
    (net (code "52") (name "VBAT") (class "Default")
      (node (ref "C2_BAT") (pin "1") (pinfunction "1_1") (pintype "passive"))
      (node (ref "MCP73831") (pin "3") (pinfunction "VBAT_3") (pintype "power_in"))
      (node (ref "Q1") (pin "3") (pinfunction "D_3") (pintype "bidirectional"))
      (node (ref "TP3") (pin "TP") (pinfunction "TP_TP") (pintype "input"))
      (node (ref "U4") (pin "2") (pinfunction "CELL_2") (pintype "power_in"))
      (node (ref "U4") (pin "3") (pinfunction "VDD_3") (pintype "power_in"))
    )
    (net (code "53") (name "VBUS") (class "Default")
      (node (ref "C1_BAT") (pin "1") (pinfunction "1_1") (pintype "passive"))
      (node (ref "C4_USB") (pin "1") (pinfunction "1_1") (pintype "passive"))
      (node (ref "C5_USB") (pin "1") (pinfunction "1_1") (pintype "passive"))
      (node (ref "CHG_LED") (pin "A") (pinfunction "A_A") (pintype "passive"))
      (node (ref "D1") (pin "5") (pinfunction "VBUS_5") (pintype "bidirectional"))
      (node (ref "D2") (pin "2") (pinfunction "ANODE_2") (pintype "bidirectional"))
      (node (ref "MCP73831") (pin "4") (pinfunction "VIN_4") (pintype "power_in"))
      (node (ref "PFMF.050.1") (pin "2") (pinfunction "2_2") (pintype "passive"))
      (node (ref "Q1") (pin "1") (pinfunction "G_1") (pintype "bidirectional"))
      (node (ref "R1_PWRUSB") (pin "2") (pinfunction "2_2") (pintype "passive"))
      (node (ref "TP14") (pin "TP") (pinfunction "TP_TP") (pintype "input"))
    )
    (net (code "54") (name "VRTC") (class "Default")
      (node (ref "C10_SUPERCAP") (pin "2") (pinfunction "2_2") (pintype "passive"))
      (node (ref "C8") (pin "1") (pinfunction "1_1") (pintype "passive"))
      (node (ref "R_CAPACITOR") (pin "1") (pinfunction "1_1") (pintype "passive"))
      (node (ref "U3") (pin "14") (pinfunction "VBAT_14") (pintype "power_in"))
    )
    (net (code "55") (name "VUSB") (class "Default")
      (node (ref "J2") (pin "A4") (pinfunction "A4_A4") (pintype "bidirectional"))
      (node (ref "J2") (pin "A9") (pinfunction "A9_A9") (pintype "bidirectional"))
      (node (ref "J2") (pin "B4") (pinfunction "B4_B4") (pintype "bidirectional"))
      (node (ref "J2") (pin "B9") (pinfunction "B9_B9") (pintype "bidirectional"))
      (node (ref "PFMF.050.1") (pin "1") (pinfunction "1_1") (pintype "passive"))
    )
    (net (code "56") (name "unconnected-(IC1-NC-Pad4)") (class "Default")
      (node (ref "IC1") (pin "4") (pinfunction "NC_4") (pintype "no_connect"))
    )
    (net (code "57") (name "unconnected-(IC4-NC-Pad4)") (class "Default")
      (node (ref "IC4") (pin "4") (pinfunction "NC_4") (pintype "no_connect"))
    )
    (net (code "58") (name "unconnected-(J1-Pad1)") (class "Default")
      (node (ref "J1") (pin "1") (pinfunction "1_1") (pintype "bidirectional"))
    )
    (net (code "59") (name "unconnected-(J1-Pad6)") (class "Default")
      (node (ref "J1") (pin "6") (pinfunction "6_6") (pintype "bidirectional"))
    )
    (net (code "60") (name "unconnected-(J1-Pad7)") (class "Default")
      (node (ref "J1") (pin "7") (pinfunction "7_7") (pintype "bidirectional"))
    )
    (net (code "61") (name "unconnected-(J2-PadA8)") (class "Default")
      (node (ref "J2") (pin "A8") (pinfunction "A8_A8") (pintype "bidirectional"))
    )
    (net (code "62") (name "unconnected-(J2-PadB8)") (class "Default")
      (node (ref "J2") (pin "B8") (pinfunction "B8_B8") (pintype "bidirectional"))
    )
    (net (code "63") (name "unconnected-(J4-DAT1-PadP8)") (class "Default")
      (node (ref "J4") (pin "P8") (pinfunction "DAT1_P8") (pintype "bidirectional"))
    )
    (net (code "64") (name "unconnected-(J4-DAT2-PadP1)") (class "Default")
      (node (ref "J4") (pin "P1") (pinfunction "DAT2_P1") (pintype "bidirectional"))
    )
    (net (code "65") (name "unconnected-(J4-DETECTION_1-PadS1)") (class "Default")
      (node (ref "J4") (pin "S1") (pinfunction "DETECTION_1_S1") (pintype "bidirectional"))
    )
    (net (code "66") (name "unconnected-(J4-DETECTION_2-PadS2)") (class "Default")
      (node (ref "J4") (pin "S2") (pinfunction "DETECTION_2_S2") (pintype "bidirectional"))
    )
    (net (code "67") (name "unconnected-(U2-NC-Pad22)") (class "Default")
      (node (ref "U2") (pin "22") (pinfunction "NC_22") (pintype "no_connect"))
    )
    (net (code "68") (name "unconnected-(U4-~{ALERT}-Pad5)") (class "Default")
      (node (ref "U4") (pin "5") (pinfunction "~{ALERT}_5") (pintype "output"))
    )
  )
)
